# 1-Schematic_PCB_Hacker_Card_1.net
KiCad netlist of a schematic drawn in EasyEDA
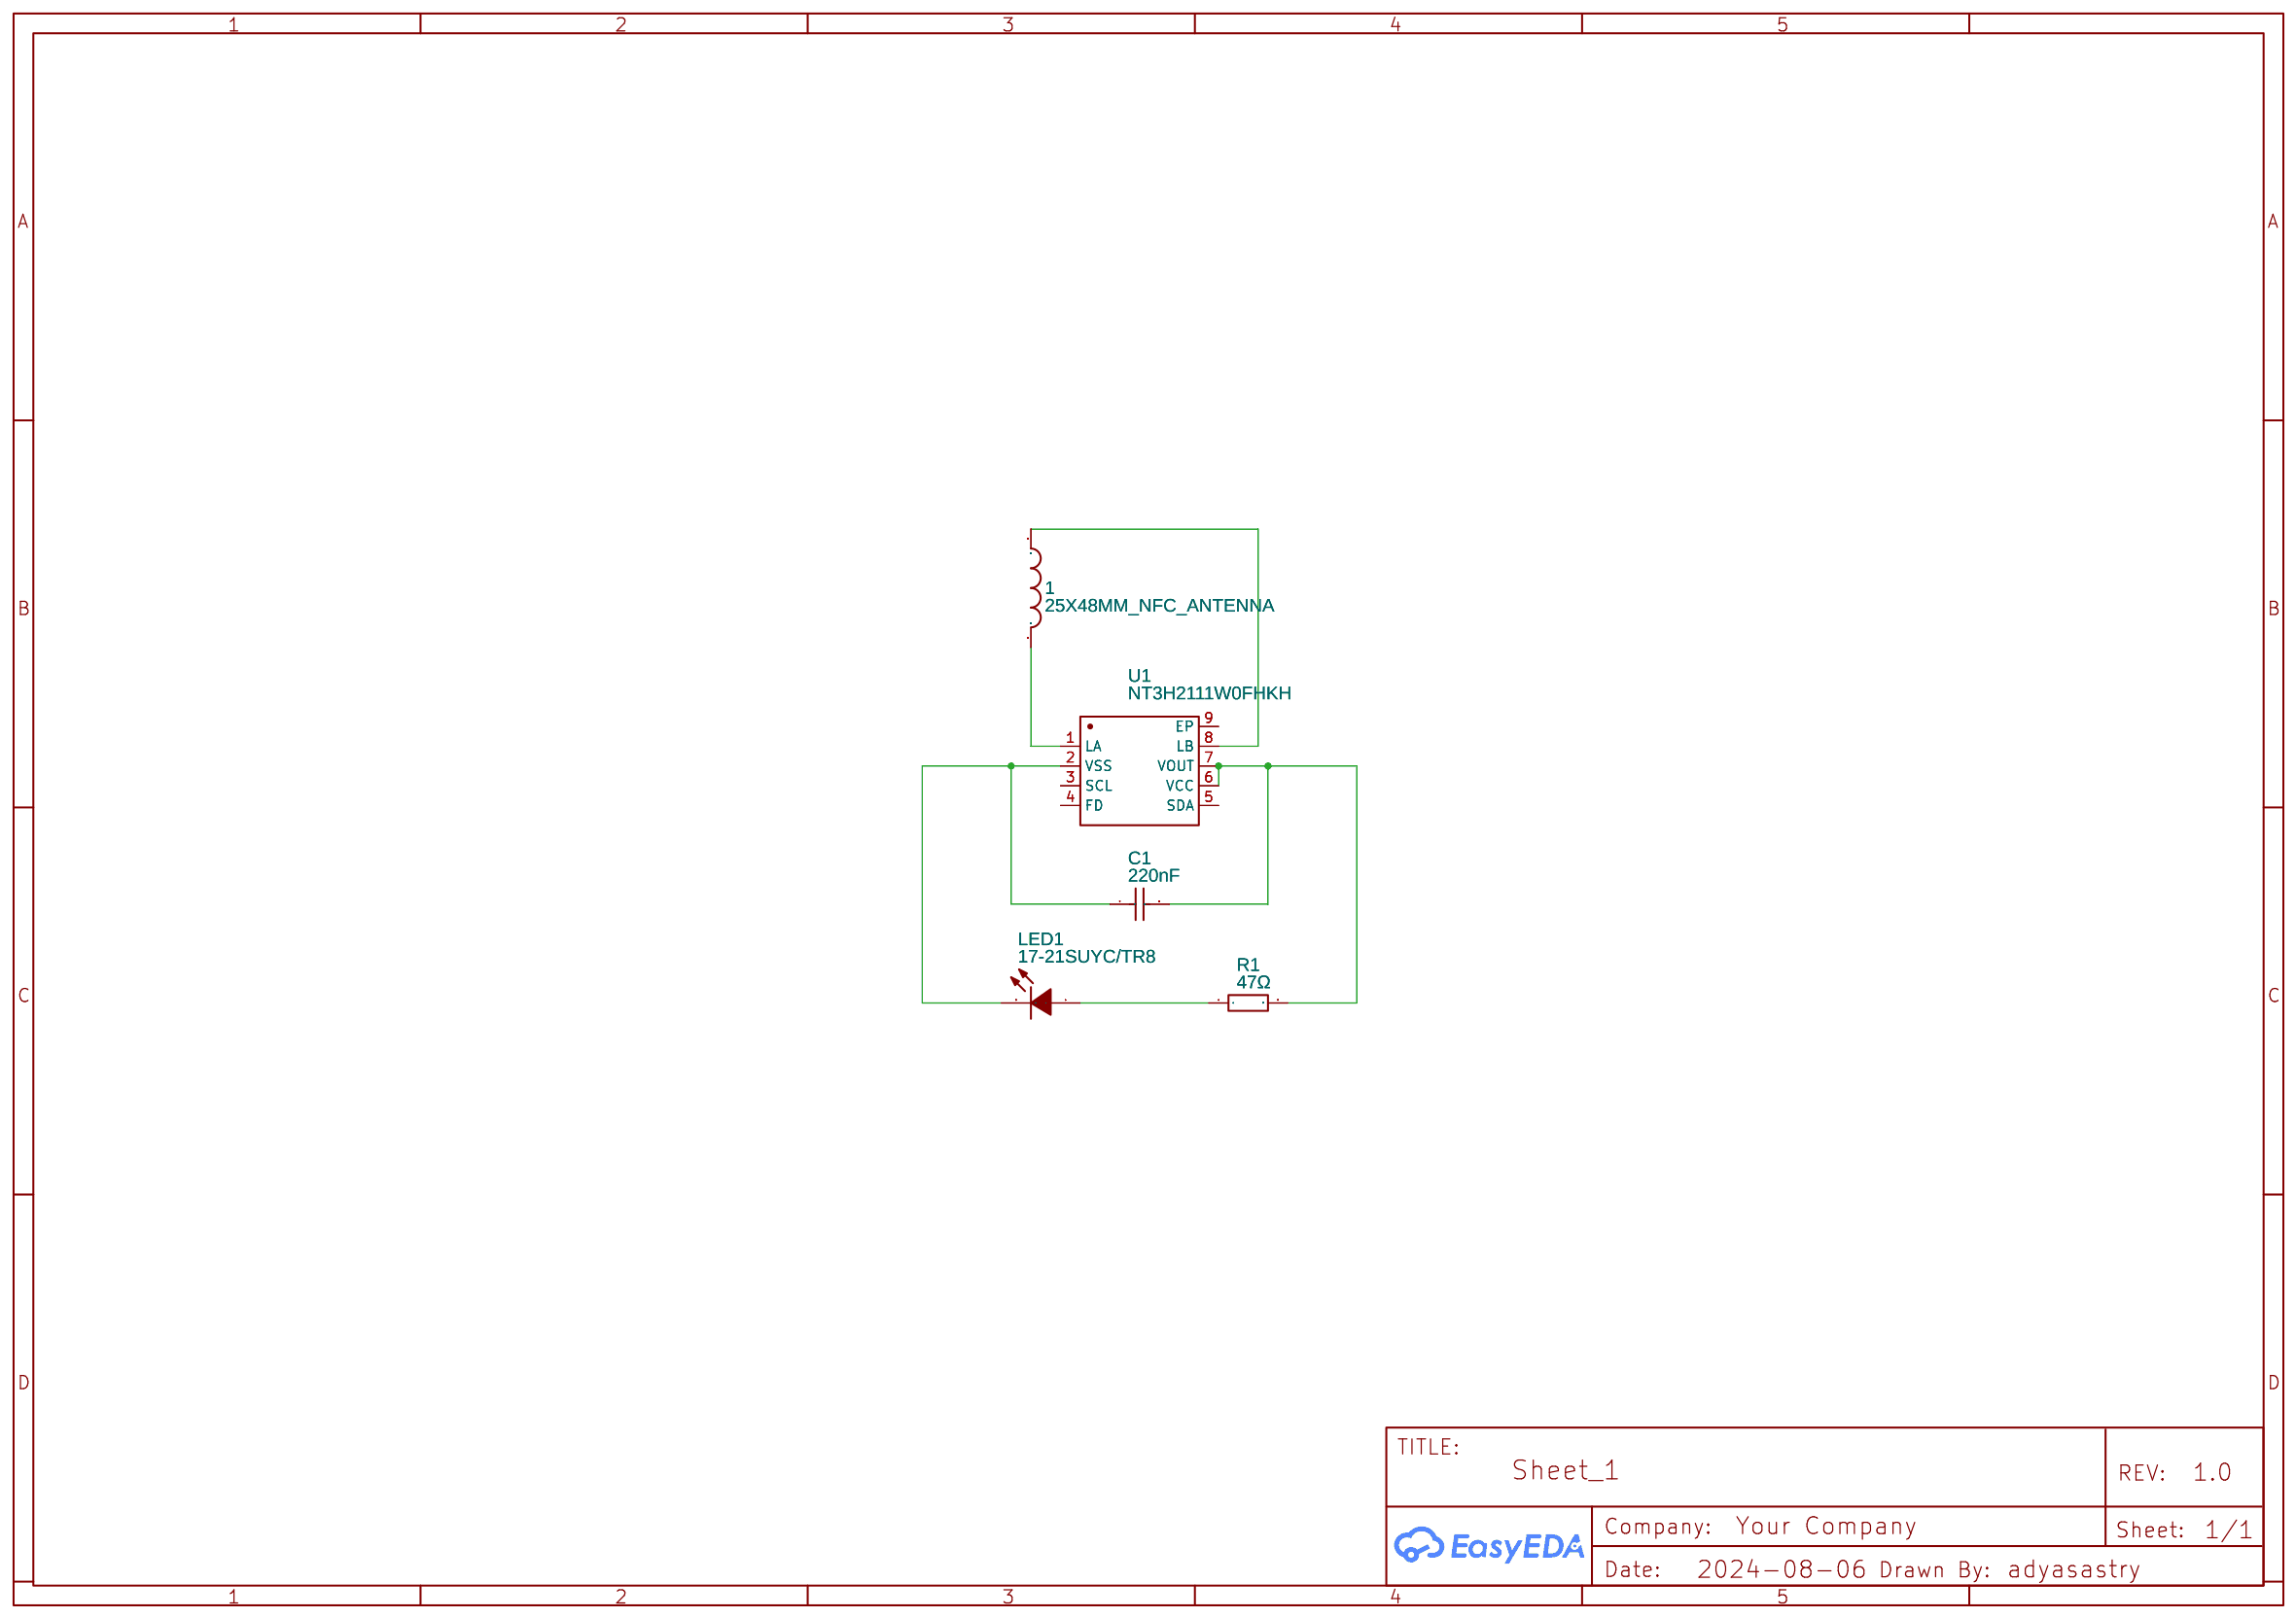
[diagram p0: schematic sheet]

(export (version "E")
  (design (tool "Eeschema 10.0.6"))
  (components
    (comp (ref "1") (value "25X48MM_NFC_ANTENNA") (libsource (lib "") (part "25X48MM_NFC_ANTENNA")))
    (comp (ref "C1")
      (value "220nF")
      (fields
        (field (name "Manufacturer Part") "CL10B224KA8NNNC")
        (field (name "Manufacturer") "SAMSUNG(三星)")
      )
      (libsource (lib "") (part "CL10B224KA8NNNC"))
    )
    (comp (ref "LED1")
      (value "17-21SUYC/TR8")
      (fields (field (name "Manufacturer Part") "KT-0805黄灯") (field (name "Manufacturer") "KENTO"))
      (libsource (lib "") (part "17-21SUYC/TR8"))
    )
    (comp (ref "R1")
      (value "47Ω")
      (fields
        (field (name "Manufacturer Part") "0603WAF470JT5E")
        (field (name "Manufacturer") "UNI-ROYAL(厚声)")
      )
      (libsource (lib "") (part "0603WAF470JT5E"))
    )
    (comp (ref "U1")
      (value "NT3H2111W0FHKH")
      (fields (field (name "Manufacturer") "NXP(恩智浦)"))
      (libsource (lib "") (part "NT3H2111W0FHKH"))
    )
  )
  (nets
    (net (code "1") (name "Net-(LED1-+)") (class "Default")
      (node (ref "LED1") (pin "1") (pinfunction "+_1") (pintype "unspecified"))
      (node (ref "R1") (pin "1") (pinfunction "1_1") (pintype "input"))
    )
    (net (code "2") (name "Net-(LED1--)") (class "Default")
      (node (ref "C1") (pin "1") (pinfunction "1_1") (pintype "input"))
      (node (ref "LED1") (pin "2") (pinfunction "-_2") (pintype "unspecified"))
      (node (ref "U1") (pin "2") (pinfunction "VSS_2") (pintype "unspecified"))
    )
    (net (code "3") (name "Net-(U1-LA)") (class "Default")
      (node (ref "1") (pin "P$2") (pinfunction "P$2_P$2") (pintype "bidirectional"))
      (node (ref "U1") (pin "1") (pinfunction "LA_1") (pintype "unspecified"))
    )
    (net (code "4") (name "Net-(U1-LB)") (class "Default")
      (node (ref "1") (pin "P$1") (pinfunction "P$1_P$1") (pintype "bidirectional"))
      (node (ref "U1") (pin "8") (pinfunction "LB_8") (pintype "unspecified"))
    )
    (net (code "5") (name "Net-(U1-VCC)") (class "Default")
      (node (ref "C1") (pin "2") (pinfunction "2_2") (pintype "input"))
      (node (ref "R1") (pin "2") (pinfunction "2_2") (pintype "input"))
      (node (ref "U1") (pin "6") (pinfunction "VCC_6") (pintype "unspecified"))
      (node (ref "U1") (pin "7") (pinfunction "VOUT_7") (pintype "unspecified"))
    )
    (net (code "6") (name "unconnected-(U1-EP-Pad9)") (class "Default")
      (node (ref "U1") (pin "9") (pinfunction "EP_9") (pintype "unspecified"))
    )
    (net (code "7") (name "unconnected-(U1-FD-Pad4)") (class "Default")
      (node (ref "U1") (pin "4") (pinfunction "FD_4") (pintype "unspecified"))
    )
    (net (code "8") (name "unconnected-(U1-SCL-Pad3)") (class "Default")
      (node (ref "U1") (pin "3") (pinfunction "SCL_3") (pintype "unspecified"))
    )
    (net (code "9") (name "unconnected-(U1-SDA-Pad5)") (class "Default")
      (node (ref "U1") (pin "5") (pinfunction "SDA_5") (pintype "unspecified"))
    )
  )
)
